# H1FR10.net
KiCad netlist of a schematic drawn in EAGLE
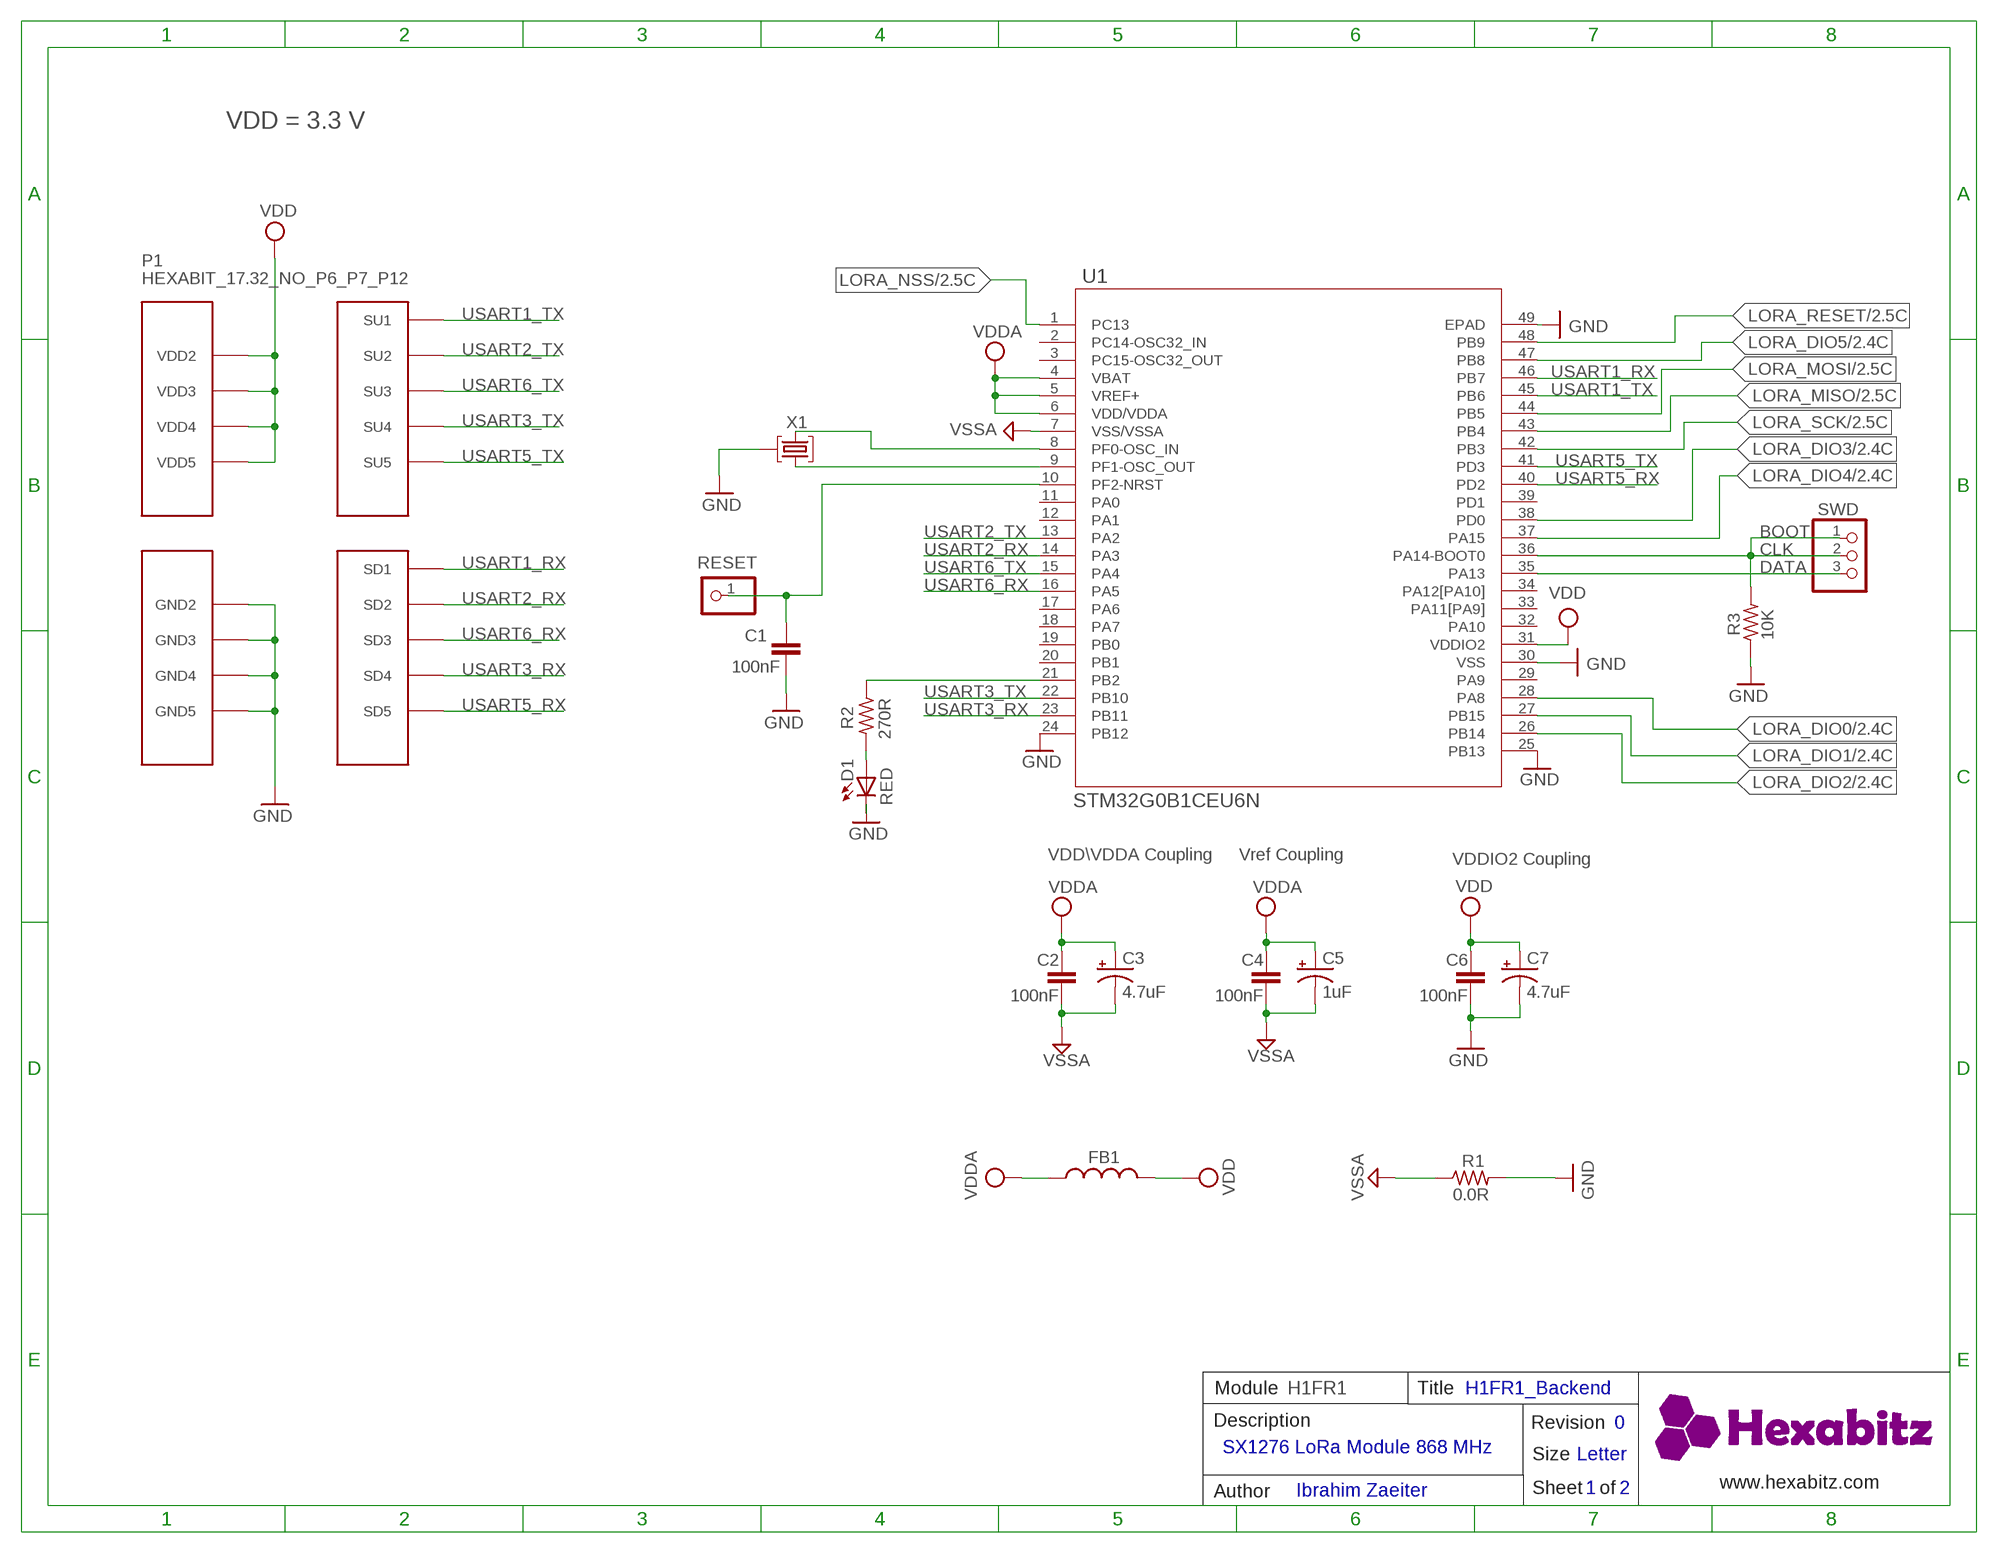
[diagram p0: schematic, sheet 1]
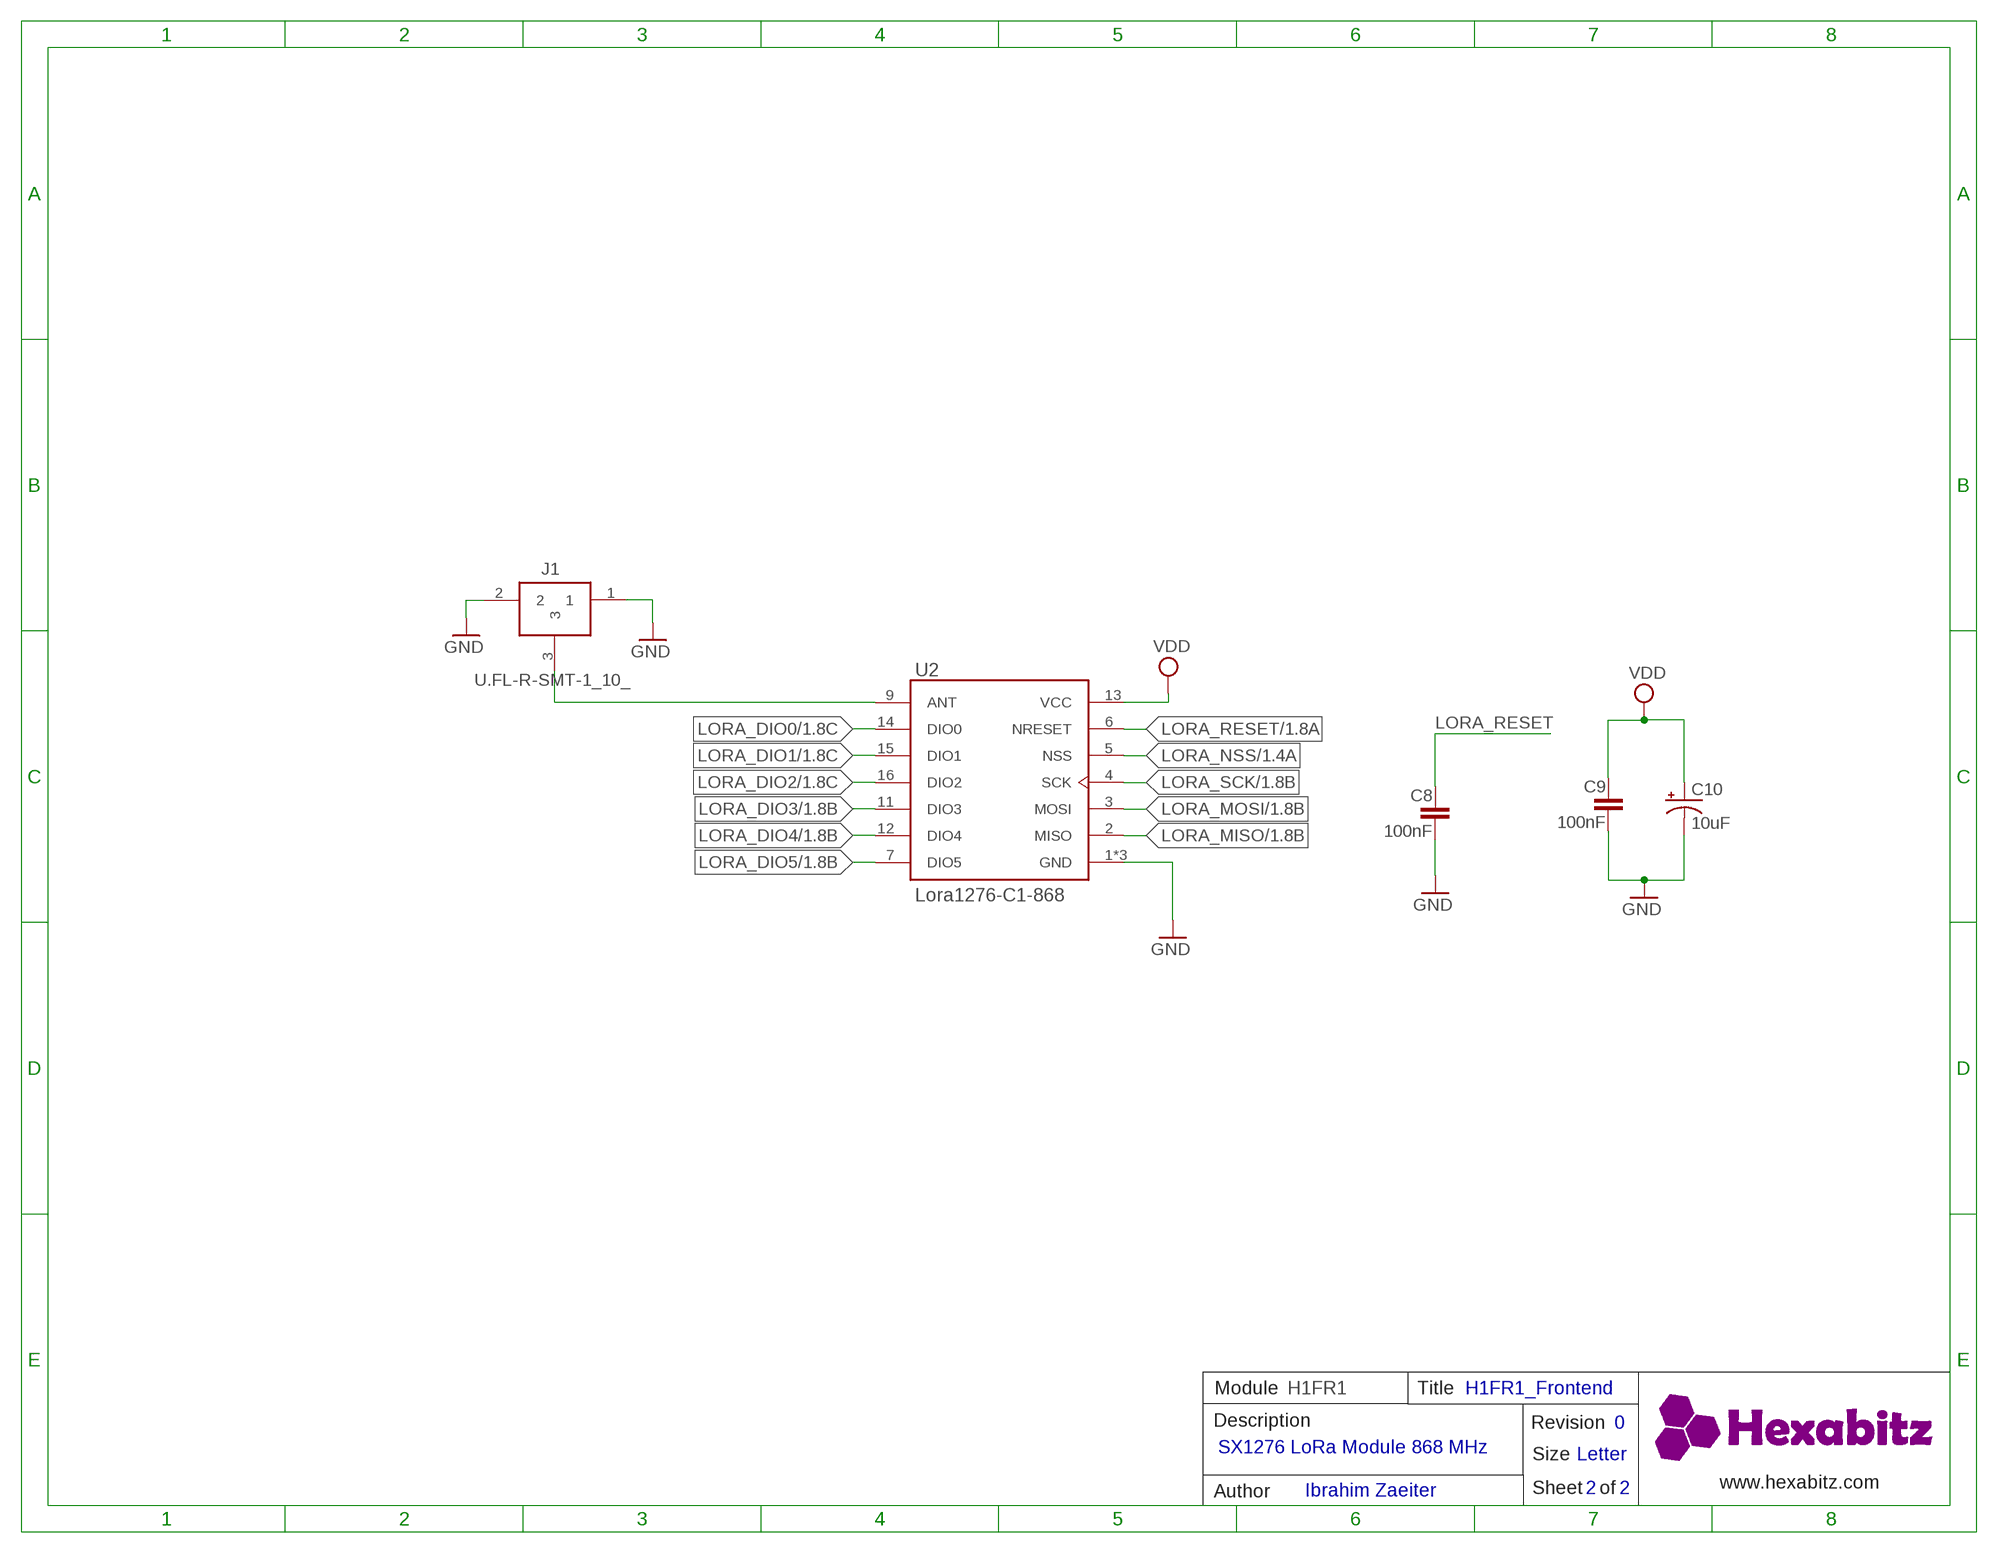
[diagram p1: schematic, sheet 2]

(export (version "E")
  (design (tool "Eeschema 10.0.6"))
  (components
    (comp (ref "C1")
      (value "100nF")
      (footprint "eagle-import:C-0603")
      (libsource (lib "eagle-import") (part "C-0603"))
    )
    (comp (ref "C2")
      (value "100nF")
      (footprint "eagle-import:C-0603")
      (libsource (lib "eagle-import") (part "C-0603"))
    )
    (comp (ref "C3")
      (value "4.7uF")
      (footprint "eagle-import:C-0805-POL")
      (libsource (lib "eagle-import") (part "C-0805-POL"))
    )
    (comp (ref "C4")
      (value "100nF")
      (footprint "eagle-import:C-0603")
      (libsource (lib "eagle-import") (part "C-0603"))
    )
    (comp (ref "C5")
      (value "1uF")
      (footprint "eagle-import:C-0805-POL")
      (libsource (lib "eagle-import") (part "C-0805-POL"))
    )
    (comp (ref "C6")
      (value "100nF")
      (footprint "eagle-import:C-0603")
      (libsource (lib "eagle-import") (part "C-0603"))
    )
    (comp (ref "C7")
      (value "4.7uF")
      (footprint "eagle-import:C-0805-POL")
      (libsource (lib "eagle-import") (part "C-0805-POL"))
    )
    (comp (ref "D1")
      (value "RED")
      (footprint "eagle-import:VLMS1300-GS08")
      (fields
        (field (name "MPN") "VLMS1300-GS08")
        (field (name "MFN") "Vishay")
        (field (name "MPN_1") "VLMS1300-GS08")
        (field (name "OCTOPART_URL") "https://octopart.com/vlms1300-gs08-vishay-21709201?r=sp&s=_gcP4_q8T1SC6PJQPTQ9yA")
      )
      (libsource (lib "eagle-import") (part "VLMS1300-GS08"))
    )
    (comp (ref "FB1")
      (value "FB-0603")
      (footprint "eagle-import:FB-0603")
      (libsource (lib "eagle-import") (part "FB-0603"))
    )
    (comp (ref "P1")
      (value "HEXABIT_17.32_NO_P6_P7_P12")
      (footprint "eagle-import:HEXABIT_17.32_NO_P6_P7_P12")
      (libsource (lib "eagle-import") (part "HEXABIT_?_NO_P6_P7_P1217.32"))
    )
    (comp (ref "R1")
      (value "0.0R")
      (footprint "eagle-import:R-0603")
      (libsource (lib "eagle-import") (part "R-0603"))
    )
    (comp (ref "R2")
      (value "270R")
      (footprint "eagle-import:R-0603")
      (libsource (lib "eagle-import") (part "R-0603"))
    )
    (comp (ref "R3")
      (value "10K")
      (footprint "eagle-import:R-0603")
      (libsource (lib "eagle-import") (part "R-0603"))
    )
    (comp (ref "RESET")
      (value "R")
      (footprint "eagle-import:1X01")
      (fields (field (name "MPN") "87227-1"))
      (libsource (lib "eagle-import") (part "PINHD-1X1"))
    )
    (comp (ref "SWD")
      (value "PINHD-1X3SWD")
      (footprint "eagle-import:SWD")
      (libsource (lib "eagle-import") (part "PINHD-1X3SWD"))
    )
    (comp (ref "U1")
      (value "STM32G0B1CEU6N")
      (footprint "eagle-import:HEXABITZ_ICS_QFN_B1CEU6_STM-L")
      (libsource (lib "eagle-import") (part "STM32G0B1CEU6N"))
    )
    (comp (ref "X1")
      (value "XTALL_CSTCE8M00G52")
      (footprint "eagle-import:XTALL_CSTCE8M00G52")
      (fields (field (name "MPN") "CSTCE8M00G52Z-R0"))
      (libsource (lib "eagle-import") (part "XTALL_CSTCE8M00G52"))
    )
    (comp (ref "C8")
      (value "100nF")
      (footprint "eagle-import:C-0603")
      (libsource (lib "eagle-import") (part "C-0603"))
    )
    (comp (ref "C9")
      (value "100nF")
      (footprint "eagle-import:C-0603")
      (libsource (lib "eagle-import") (part "C-0603"))
    )
    (comp (ref "C10")
      (value "10uF")
      (footprint "eagle-import:C-1210-POL")
      (libsource (lib "eagle-import") (part "C-1210-POL"))
    )
    (comp (ref "J1")
      (value "U.FL-R-SMT-1_10_")
      (footprint "eagle-import:U.FL-R-SMT-1(10)")
      (fields
        (field (name "MANUFACTURER_PART_NUMBER") "U.FL-R-SMT-1(10)")
        (field (name "MOUSER_PART_NUMBER") "798-U.FL-R-SMT-110")
      )
      (libsource (lib "eagle-import") (part "U.FL-R-SMT-1_10_"))
    )
    (comp (ref "U2")
      (value "Lora1276-C1-868")
      (footprint "eagle-import:LORA127X-C1")
      (fields (field (name "MF") "AI-Thinker") (field (name "MP") "ESP8266-12E/ESP-12E"))
      (libsource (lib "eagle-import") (part "LORA127X-C1"))
    )
  )
  (nets
    (net (code "1") (name "CLK") (class "Default")
      (node (ref "R3") (pin "2") (pinfunction "2_2") (pintype "passive"))
      (node (ref "SWD") (pin "1") (pinfunction "1_1") (pintype "passive"))
      (node (ref "SWD") (pin "2") (pinfunction "2_2") (pintype "passive"))
      (node (ref "U1") (pin "36") (pinfunction "PA14-BOOT0_36") (pintype "bidirectional"))
    )
    (net (code "2") (name "DATA") (class "Default")
      (node (ref "SWD") (pin "3") (pinfunction "3_3") (pintype "passive"))
      (node (ref "U1") (pin "35") (pinfunction "PA13_35") (pintype "bidirectional"))
    )
    (net (code "3") (name "GND") (class "Default")
      (node (ref "C1") (pin "2") (pinfunction "2_2") (pintype "passive"))
      (node (ref "C10") (pin "2") (pinfunction "-_2") (pintype "passive"))
      (node (ref "C6") (pin "2") (pinfunction "2_2") (pintype "passive"))
      (node (ref "C7") (pin "2") (pinfunction "-_2") (pintype "passive"))
      (node (ref "C8") (pin "2") (pinfunction "2_2") (pintype "passive"))
      (node (ref "C9") (pin "2") (pinfunction "2_2") (pintype "passive"))
      (node (ref "D1") (pin "C") (pinfunction "C_C") (pintype "passive"))
      (node (ref "J1") (pin "1") (pinfunction "1_1") (pintype "bidirectional"))
      (node (ref "J1") (pin "2") (pinfunction "2_2") (pintype "bidirectional"))
      (node (ref "P1") (pin "PAD_PD10") (pinfunction "GND4_PAD_PD10") (pintype "power_in"))
      (node (ref "P1") (pin "PAD_PD11") (pinfunction "GND5_PAD_PD11") (pintype "power_in"))
      (node (ref "P1") (pin "PAD_PD8") (pinfunction "GND2_PAD_PD8") (pintype "power_in"))
      (node (ref "P1") (pin "PAD_PD9") (pinfunction "GND3_PAD_PD9") (pintype "power_in"))
      (node (ref "R1") (pin "2") (pinfunction "2_2") (pintype "passive"))
      (node (ref "R3") (pin "1") (pinfunction "1_1") (pintype "passive"))
      (node (ref "U1") (pin "24") (pinfunction "PB12_24") (pintype "bidirectional"))
      (node (ref "U1") (pin "25") (pinfunction "PB13_25") (pintype "bidirectional"))
      (node (ref "U1") (pin "30") (pinfunction "VSS_30") (pintype "passive"))
      (node (ref "U1") (pin "49") (pinfunction "EPAD_49") (pintype "passive"))
      (node (ref "U2") (pin "1") (pinfunction "GND_1") (pintype "power_in"))
      (node (ref "U2") (pin "10") (pinfunction "GND_10") (pintype "power_in"))
      (node (ref "U2") (pin "8") (pinfunction "GND_8") (pintype "power_in"))
      (node (ref "X1") (pin "P$2") (pinfunction "2_P$2") (pintype "passive"))
    )
    (net (code "4") (name "LORA_DIO0") (class "Default")
      (node (ref "U1") (pin "28") (pinfunction "PA8_28") (pintype "bidirectional"))
      (node (ref "U2") (pin "14") (pinfunction "DIO0_14") (pintype "bidirectional"))
    )
    (net (code "5") (name "LORA_DIO1") (class "Default")
      (node (ref "U1") (pin "27") (pinfunction "PB15_27") (pintype "bidirectional"))
      (node (ref "U2") (pin "15") (pinfunction "DIO1_15") (pintype "bidirectional"))
    )
    (net (code "6") (name "LORA_DIO2") (class "Default")
      (node (ref "U1") (pin "26") (pinfunction "PB14_26") (pintype "bidirectional"))
      (node (ref "U2") (pin "16") (pinfunction "DIO2_16") (pintype "bidirectional"))
    )
    (net (code "7") (name "LORA_DIO3") (class "Default")
      (node (ref "U1") (pin "38") (pinfunction "PD0_38") (pintype "bidirectional"))
      (node (ref "U2") (pin "11") (pinfunction "DIO3_11") (pintype "bidirectional"))
    )
    (net (code "8") (name "LORA_DIO4") (class "Default")
      (node (ref "U1") (pin "37") (pinfunction "PA15_37") (pintype "bidirectional"))
      (node (ref "U2") (pin "12") (pinfunction "DIO4_12") (pintype "bidirectional"))
    )
    (net (code "9") (name "LORA_DIO5") (class "Default")
      (node (ref "U1") (pin "47") (pinfunction "PB8_47") (pintype "bidirectional"))
      (node (ref "U2") (pin "7") (pinfunction "DIO5_7") (pintype "bidirectional"))
    )
    (net (code "10") (name "LORA_MISO") (class "Default")
      (node (ref "U1") (pin "43") (pinfunction "PB4_43") (pintype "bidirectional"))
      (node (ref "U2") (pin "2") (pinfunction "MISO_2") (pintype "bidirectional"))
    )
    (net (code "11") (name "LORA_MOSI") (class "Default")
      (node (ref "U1") (pin "44") (pinfunction "PB5_44") (pintype "bidirectional"))
      (node (ref "U2") (pin "3") (pinfunction "MOSI_3") (pintype "bidirectional"))
    )
    (net (code "12") (name "LORA_NSS") (class "Default")
      (node (ref "U1") (pin "1") (pinfunction "PC13_1") (pintype "bidirectional"))
      (node (ref "U2") (pin "5") (pinfunction "NSS_5") (pintype "input"))
    )
    (net (code "13") (name "LORA_RESET") (class "Default")
      (node (ref "C8") (pin "1") (pinfunction "1_1") (pintype "passive"))
      (node (ref "U1") (pin "48") (pinfunction "PB9_48") (pintype "bidirectional"))
      (node (ref "U2") (pin "6") (pinfunction "NRESET_6") (pintype "input"))
    )
    (net (code "14") (name "LORA_SCK") (class "Default")
      (node (ref "U1") (pin "42") (pinfunction "PB3_42") (pintype "bidirectional"))
      (node (ref "U2") (pin "4") (pinfunction "SCK_4") (pintype "input"))
    )
    (net (code "15") (name "Net-(D1-PadA)") (class "Default")
      (node (ref "D1") (pin "A") (pinfunction "A_A") (pintype "passive"))
      (node (ref "R2") (pin "2") (pinfunction "2_2") (pintype "passive"))
    )
    (net (code "16") (name "Net-(U1-PB2)") (class "Default")
      (node (ref "R2") (pin "1") (pinfunction "1_1") (pintype "passive"))
      (node (ref "U1") (pin "21") (pinfunction "PB2_21") (pintype "bidirectional"))
    )
    (net (code "17") (name "Net-(U1-PF0-OSC_IN)") (class "Default")
      (node (ref "U1") (pin "8") (pinfunction "PF0-OSC_IN_8") (pintype "bidirectional"))
      (node (ref "X1") (pin "P$3") (pinfunction "3_P$3") (pintype "passive"))
    )
    (net (code "18") (name "Net-(U1-PF1-OSC_OUT)") (class "Default")
      (node (ref "U1") (pin "9") (pinfunction "PF1-OSC_OUT_9") (pintype "bidirectional"))
      (node (ref "X1") (pin "P$1") (pinfunction "1_P$1") (pintype "passive"))
    )
    (net (code "19") (name "Net-(U1-PF2-NRST)") (class "Default")
      (node (ref "C1") (pin "1") (pinfunction "1_1") (pintype "passive"))
      (node (ref "RESET") (pin "1") (pinfunction "1_1") (pintype "passive"))
      (node (ref "U1") (pin "10") (pinfunction "PF2-NRST_10") (pintype "bidirectional"))
    )
    (net (code "20") (name "Net-(U2-ANT)") (class "Default")
      (node (ref "J1") (pin "3") (pinfunction "3_3") (pintype "bidirectional"))
      (node (ref "U2") (pin "9") (pinfunction "ANT_9") (pintype "passive"))
    )
    (net (code "21") (name "USART1_RX") (class "Default")
      (node (ref "P1") (pin "PAD_PD1") (pinfunction "SD1_PAD_PD1") (pintype "bidirectional"))
      (node (ref "U1") (pin "46") (pinfunction "PB7_46") (pintype "bidirectional"))
    )
    (net (code "22") (name "USART1_TX") (class "Default")
      (node (ref "P1") (pin "PAD_PU1") (pinfunction "SU1_PAD_PU1") (pintype "bidirectional"))
      (node (ref "U1") (pin "45") (pinfunction "PB6_45") (pintype "bidirectional"))
    )
    (net (code "23") (name "USART2_RX") (class "Default")
      (node (ref "P1") (pin "PAD_PD2") (pinfunction "SD2_PAD_PD2") (pintype "bidirectional"))
      (node (ref "U1") (pin "14") (pinfunction "PA3_14") (pintype "bidirectional"))
    )
    (net (code "24") (name "USART2_TX") (class "Default")
      (node (ref "P1") (pin "PAD_PU2") (pinfunction "SU2_PAD_PU2") (pintype "bidirectional"))
      (node (ref "U1") (pin "13") (pinfunction "PA2_13") (pintype "bidirectional"))
    )
    (net (code "25") (name "USART3_RX") (class "Default")
      (node (ref "P1") (pin "PAD_PD4") (pinfunction "SD4_PAD_PD4") (pintype "bidirectional"))
      (node (ref "U1") (pin "23") (pinfunction "PB11_23") (pintype "bidirectional"))
    )
    (net (code "26") (name "USART3_TX") (class "Default")
      (node (ref "P1") (pin "PAD_PU4") (pinfunction "SU4_PAD_PU4") (pintype "bidirectional"))
      (node (ref "U1") (pin "22") (pinfunction "PB10_22") (pintype "bidirectional"))
    )
    (net (code "27") (name "USART5_RX") (class "Default")
      (node (ref "P1") (pin "PAD_PD5") (pinfunction "SD5_PAD_PD5") (pintype "bidirectional"))
      (node (ref "U1") (pin "40") (pinfunction "PD2_40") (pintype "bidirectional"))
    )
    (net (code "28") (name "USART5_TX") (class "Default")
      (node (ref "P1") (pin "PAD_PU5") (pinfunction "SU5_PAD_PU5") (pintype "bidirectional"))
      (node (ref "U1") (pin "41") (pinfunction "PD3_41") (pintype "bidirectional"))
    )
    (net (code "29") (name "USART6_RX") (class "Default")
      (node (ref "P1") (pin "PAD_PD3") (pinfunction "SD3_PAD_PD3") (pintype "bidirectional"))
      (node (ref "U1") (pin "16") (pinfunction "PA5_16") (pintype "bidirectional"))
    )
    (net (code "30") (name "USART6_TX") (class "Default")
      (node (ref "P1") (pin "PAD_PU3") (pinfunction "SU3_PAD_PU3") (pintype "bidirectional"))
      (node (ref "U1") (pin "15") (pinfunction "PA4_15") (pintype "bidirectional"))
    )
    (net (code "31") (name "VDD") (class "Default")
      (node (ref "C10") (pin "1") (pinfunction "+_1") (pintype "passive"))
      (node (ref "C6") (pin "1") (pinfunction "1_1") (pintype "passive"))
      (node (ref "C7") (pin "1") (pinfunction "+_1") (pintype "passive"))
      (node (ref "C9") (pin "1") (pinfunction "1_1") (pintype "passive"))
      (node (ref "FB1") (pin "2") (pinfunction "2_2") (pintype "passive"))
      (node (ref "P1") (pin "PAD_PU10") (pinfunction "VDD4_PAD_PU10") (pintype "power_in"))
      (node (ref "P1") (pin "PAD_PU11") (pinfunction "VDD5_PAD_PU11") (pintype "power_in"))
      (node (ref "P1") (pin "PAD_PU8") (pinfunction "VDD2_PAD_PU8") (pintype "power_in"))
      (node (ref "P1") (pin "PAD_PU9") (pinfunction "VDD3_PAD_PU9") (pintype "power_in"))
      (node (ref "U1") (pin "31") (pinfunction "VDDIO2_31") (pintype "power_in"))
      (node (ref "U2") (pin "13") (pinfunction "VCC_13") (pintype "power_in"))
    )
    (net (code "32") (name "VDDA") (class "Default")
      (node (ref "C2") (pin "1") (pinfunction "1_1") (pintype "passive"))
      (node (ref "C3") (pin "1") (pinfunction "+_1") (pintype "passive"))
      (node (ref "C4") (pin "1") (pinfunction "1_1") (pintype "passive"))
      (node (ref "C5") (pin "1") (pinfunction "+_1") (pintype "passive"))
      (node (ref "FB1") (pin "1") (pinfunction "1_1") (pintype "passive"))
      (node (ref "U1") (pin "4") (pinfunction "VBAT_4") (pintype "power_in"))
      (node (ref "U1") (pin "5") (pinfunction "VREF+_5") (pintype "power_in"))
      (node (ref "U1") (pin "6") (pinfunction "VDD/VDDA_6") (pintype "power_in"))
    )
    (net (code "33") (name "VSSA") (class "Default")
      (node (ref "C2") (pin "2") (pinfunction "2_2") (pintype "passive"))
      (node (ref "C3") (pin "2") (pinfunction "-_2") (pintype "passive"))
      (node (ref "C4") (pin "2") (pinfunction "2_2") (pintype "passive"))
      (node (ref "C5") (pin "2") (pinfunction "-_2") (pintype "passive"))
      (node (ref "R1") (pin "1") (pinfunction "1_1") (pintype "passive"))
      (node (ref "U1") (pin "7") (pinfunction "VSS/VSSA_7") (pintype "passive"))
    )
    (net (code "34") (name "unconnected-(U1-PA0-Pad11)") (class "Default")
      (node (ref "U1") (pin "11") (pinfunction "PA0_11") (pintype "bidirectional"))
    )
    (net (code "35") (name "unconnected-(U1-PA1-Pad12)") (class "Default")
      (node (ref "U1") (pin "12") (pinfunction "PA1_12") (pintype "bidirectional"))
    )
    (net (code "36") (name "unconnected-(U1-PA6-Pad17)") (class "Default")
      (node (ref "U1") (pin "17") (pinfunction "PA6_17") (pintype "bidirectional"))
    )
    (net (code "37") (name "unconnected-(U1-PA7-Pad18)") (class "Default")
      (node (ref "U1") (pin "18") (pinfunction "PA7_18") (pintype "bidirectional"))
    )
    (net (code "38") (name "unconnected-(U1-PA9-Pad29)") (class "Default")
      (node (ref "U1") (pin "29") (pinfunction "PA9_29") (pintype "bidirectional"))
    )
    (net (code "39") (name "unconnected-(U1-PA10-Pad32)") (class "Default")
      (node (ref "U1") (pin "32") (pinfunction "PA10_32") (pintype "bidirectional"))
    )
    (net (code "40") (name "unconnected-(U1-PA11[PA9]-Pad33)") (class "Default")
      (node (ref "U1") (pin "33") (pinfunction "PA11[PA9]_33") (pintype "bidirectional"))
    )
    (net (code "41") (name "unconnected-(U1-PA12[PA10]-Pad34)") (class "Default")
      (node (ref "U1") (pin "34") (pinfunction "PA12[PA10]_34") (pintype "bidirectional"))
    )
    (net (code "42") (name "unconnected-(U1-PB0-Pad19)") (class "Default")
      (node (ref "U1") (pin "19") (pinfunction "PB0_19") (pintype "bidirectional"))
    )
    (net (code "43") (name "unconnected-(U1-PB1-Pad20)") (class "Default")
      (node (ref "U1") (pin "20") (pinfunction "PB1_20") (pintype "bidirectional"))
    )
    (net (code "44") (name "unconnected-(U1-PC14-OSC32_IN-Pad2)") (class "Default")
      (node (ref "U1") (pin "2") (pinfunction "PC14-OSC32_IN_2") (pintype "bidirectional"))
    )
    (net (code "45") (name "unconnected-(U1-PC15-OSC32_OUT-Pad3)") (class "Default")
      (node (ref "U1") (pin "3") (pinfunction "PC15-OSC32_OUT_3") (pintype "bidirectional"))
    )
    (net (code "46") (name "unconnected-(U1-PD1-Pad39)") (class "Default")
      (node (ref "U1") (pin "39") (pinfunction "PD1_39") (pintype "bidirectional"))
    )
  )
)
